# Versie_4.net
KiCad netlist of a schematic drawn in EAGLE
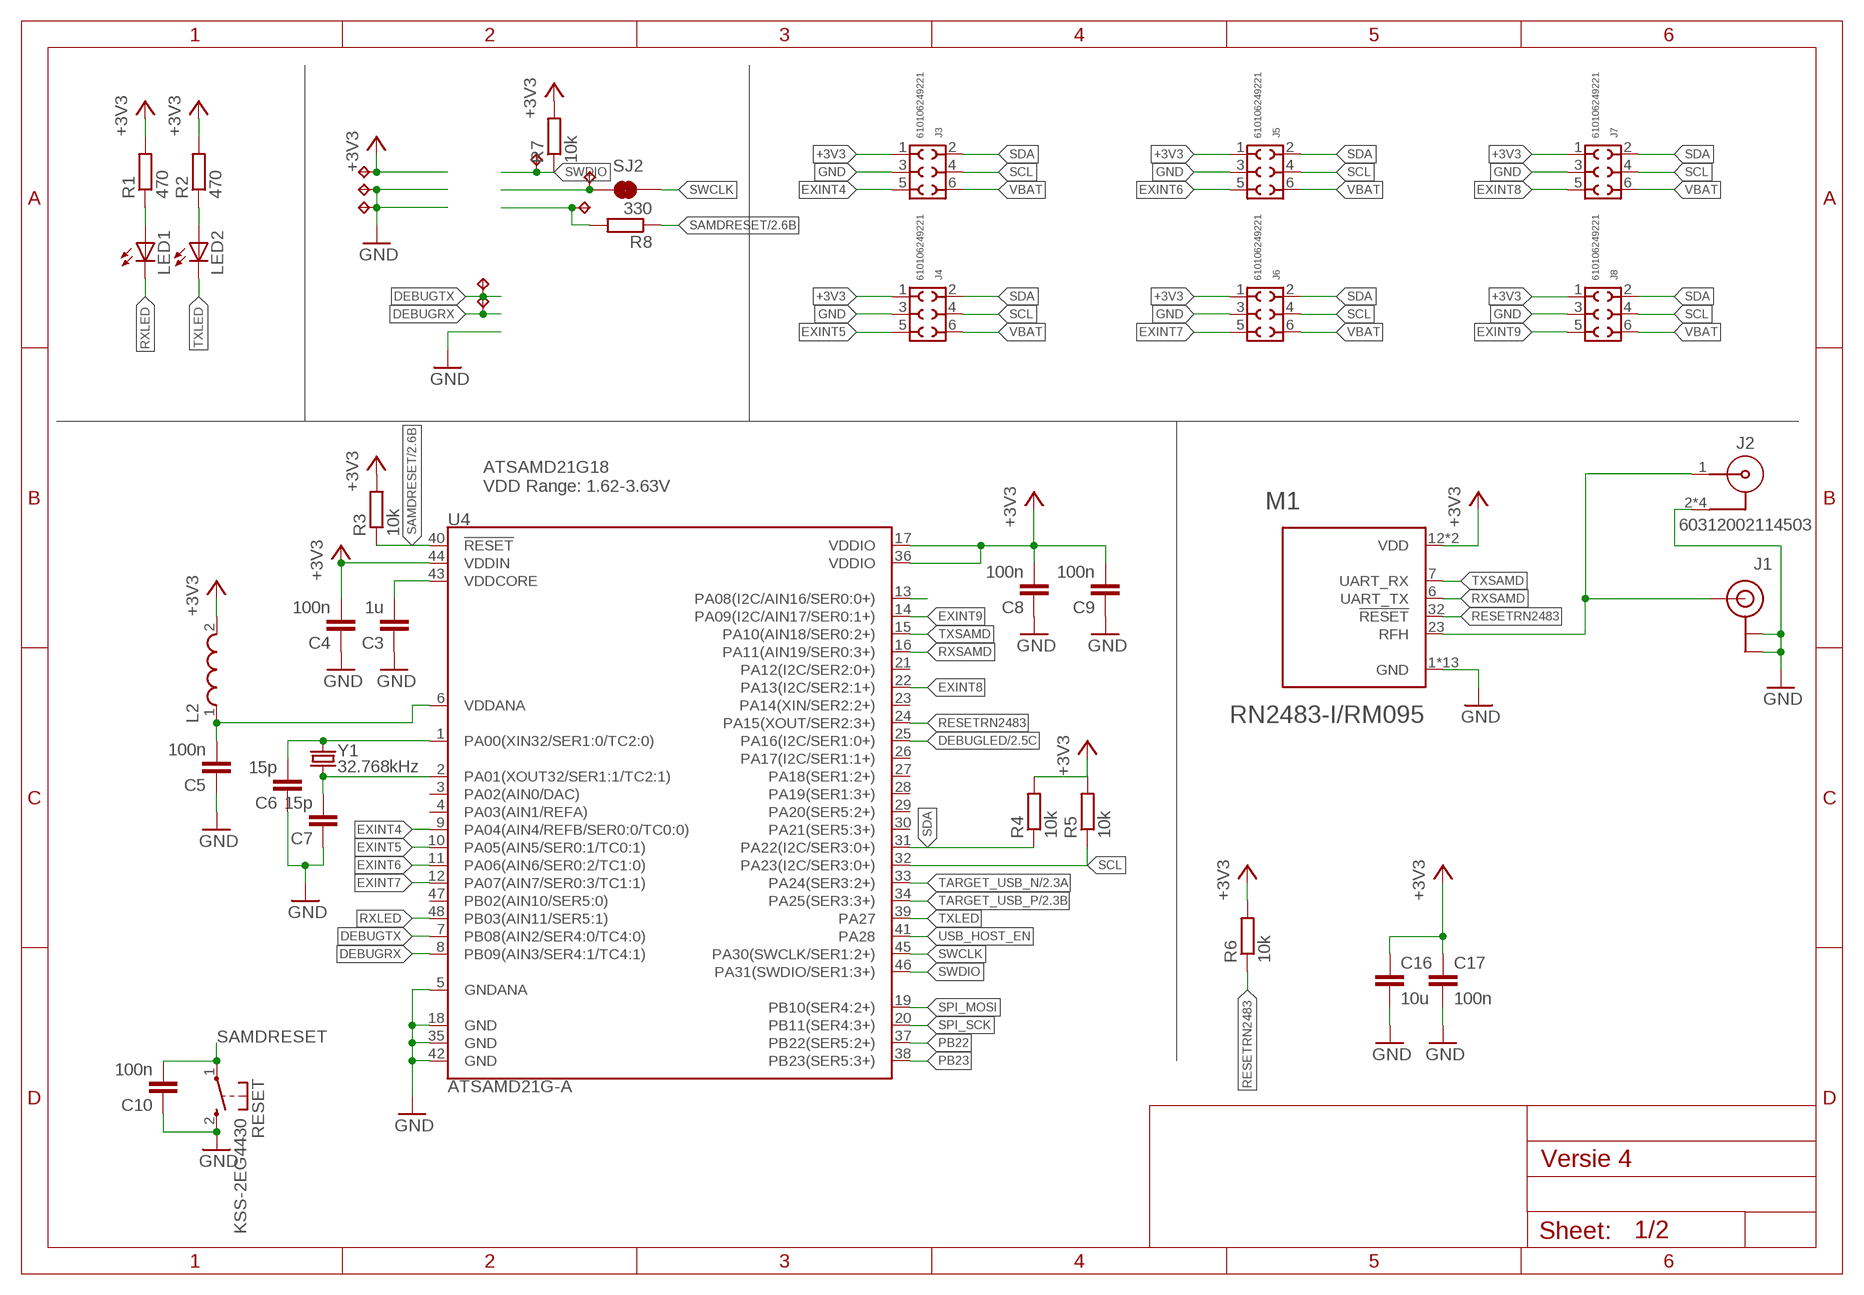
[diagram p0: schematic, sheet 1]
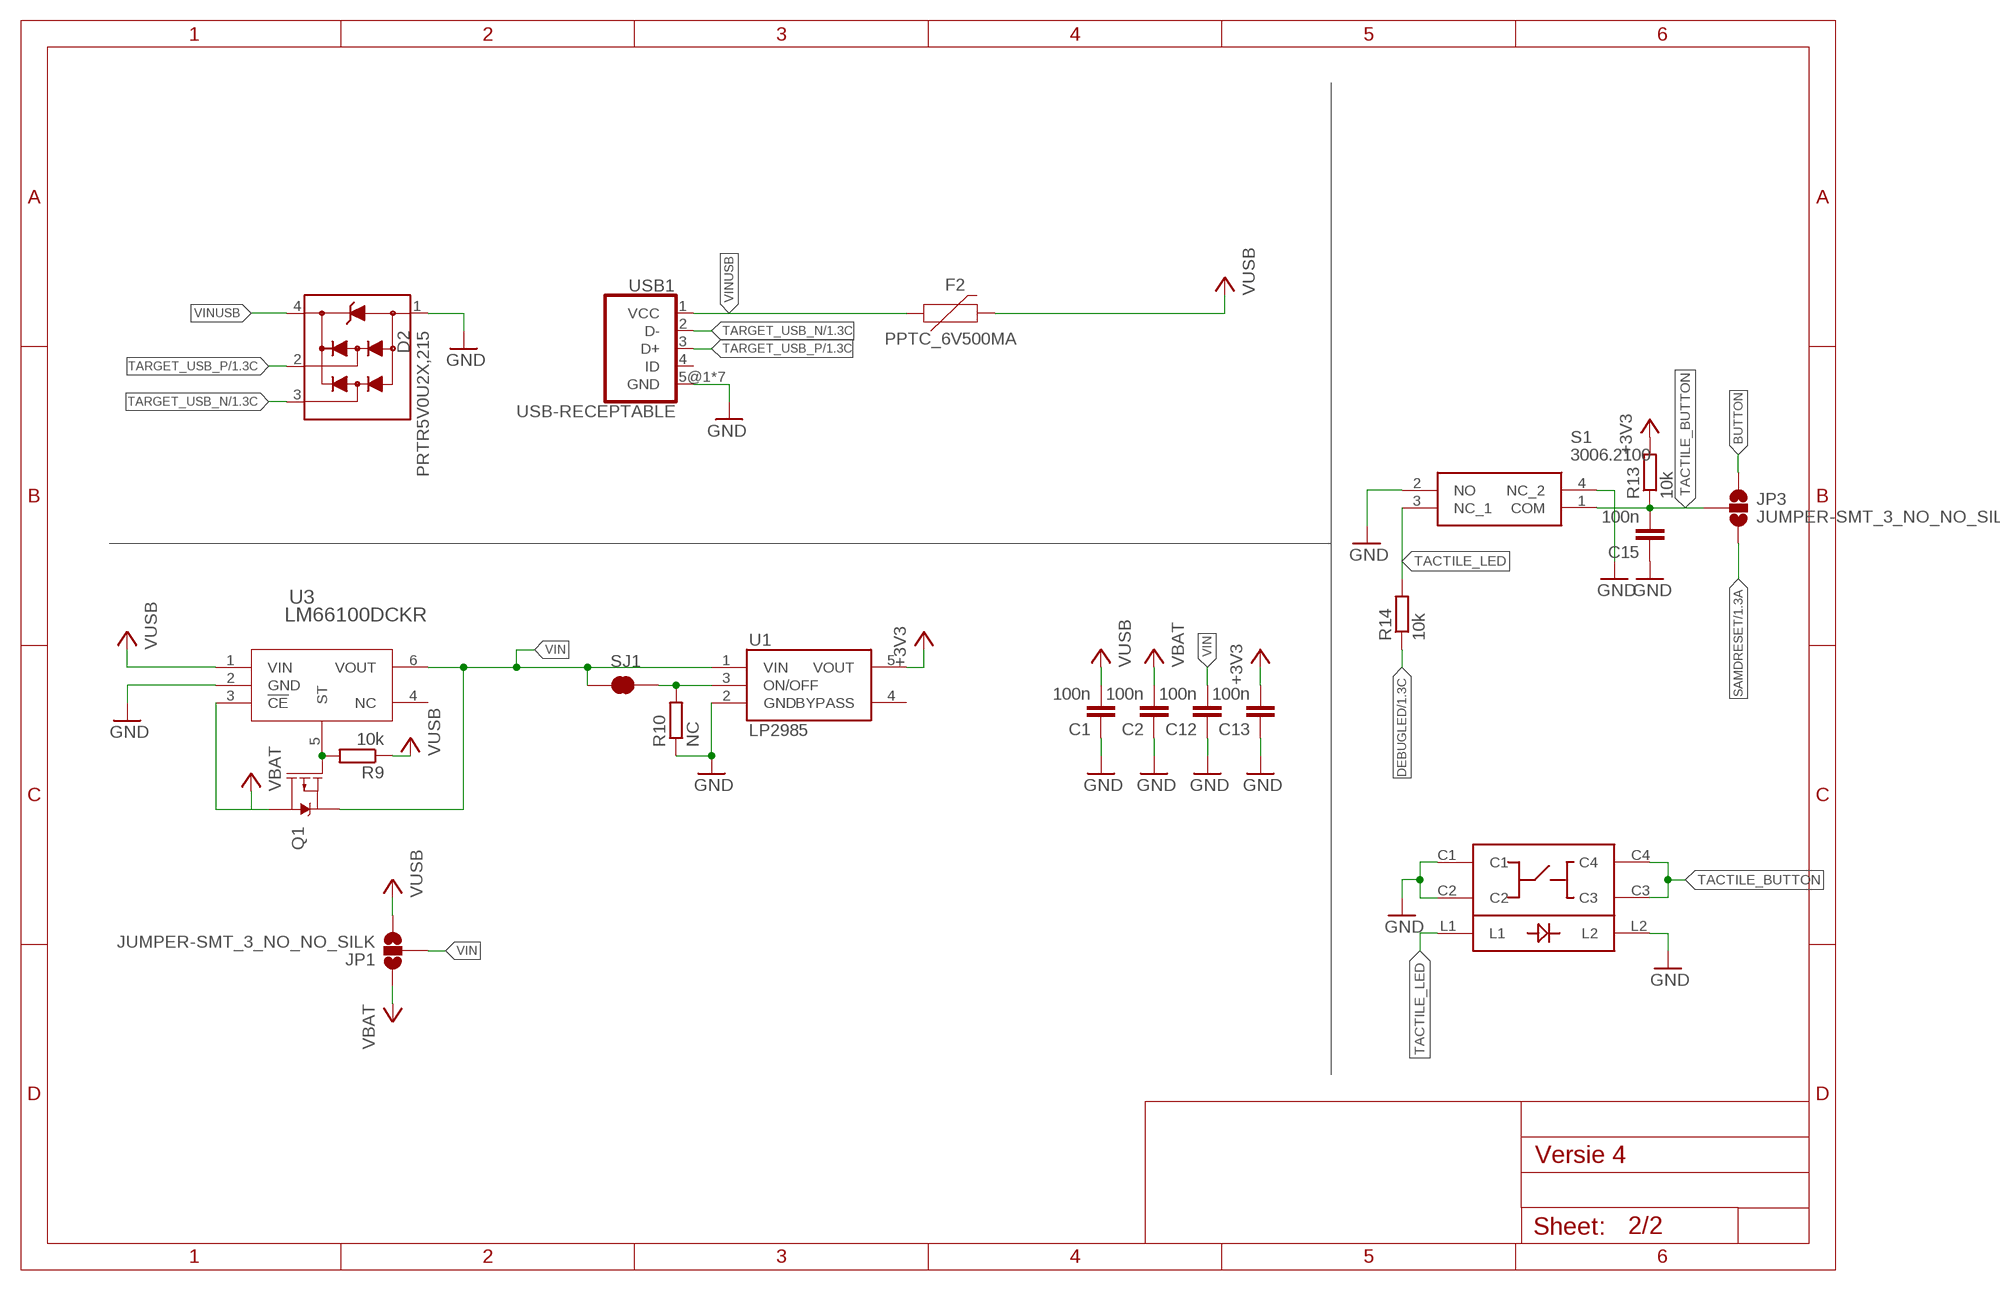
[diagram p1: schematic, sheet 2]

(export (version "E")
  (design (tool "Eeschema 10.0.6"))
  (components
    (comp (ref "C3")
      (value "1u")
      (footprint "eagle-import:C0603")
      (libsource (lib "eagle-import") (part "C-EUC0603"))
    )
    (comp (ref "C4")
      (value "100n")
      (footprint "eagle-import:C0603")
      (libsource (lib "eagle-import") (part "C-EUC0603"))
    )
    (comp (ref "C5")
      (value "100n")
      (footprint "eagle-import:C0603")
      (libsource (lib "eagle-import") (part "C-EUC0603"))
    )
    (comp (ref "C6")
      (value "15p")
      (footprint "eagle-import:C0603")
      (libsource (lib "eagle-import") (part "C-EUC0603"))
    )
    (comp (ref "C7")
      (value "15p")
      (footprint "eagle-import:C0603")
      (libsource (lib "eagle-import") (part "C-EUC0603"))
    )
    (comp (ref "C8")
      (value "100n")
      (footprint "eagle-import:C0603")
      (libsource (lib "eagle-import") (part "C-EUC0603"))
    )
    (comp (ref "C9")
      (value "100n")
      (footprint "eagle-import:C0603")
      (libsource (lib "eagle-import") (part "C-EUC0603"))
    )
    (comp (ref "C10")
      (value "100n")
      (footprint "eagle-import:C0603")
      (libsource (lib "eagle-import") (part "C-EUC0603"))
    )
    (comp (ref "C16")
      (value "10u")
      (footprint "eagle-import:C0805")
      (libsource (lib "eagle-import") (part "C-EUC0805"))
    )
    (comp (ref "C17")
      (value "100n")
      (footprint "eagle-import:C0603")
      (libsource (lib "eagle-import") (part "C-EUC0603"))
    )
    (comp (ref "J1")
      (value "U.FL")
      (footprint "eagle-import:U.FL")
      (libsource (lib "eagle-import") (part "U.FL"))
    )
    (comp (ref "J2")
      (value "60312002114503")
      (footprint "eagle-import:60312002114503")
      (libsource (lib "eagle-import") (part "60312002114503"))
    )
    (comp (ref "J3")
      (value "610106249221")
      (footprint "eagle-import:610106249221")
      (libsource (lib "eagle-import") (part "6101XX249221_610106249221"))
    )
    (comp (ref "J4")
      (value "610106249221")
      (footprint "eagle-import:610106249221")
      (libsource (lib "eagle-import") (part "6101XX249221_610106249221"))
    )
    (comp (ref "J5")
      (value "610106249221")
      (footprint "eagle-import:610106249221")
      (libsource (lib "eagle-import") (part "6101XX249221_610106249221"))
    )
    (comp (ref "J6")
      (value "610106249221")
      (footprint "eagle-import:610106249221")
      (libsource (lib "eagle-import") (part "6101XX249221_610106249221"))
    )
    (comp (ref "J7")
      (value "610106249221")
      (footprint "eagle-import:610106249221")
      (libsource (lib "eagle-import") (part "6101XX249221_610106249221"))
    )
    (comp (ref "J8")
      (value "610106249221")
      (footprint "eagle-import:610106249221")
      (libsource (lib "eagle-import") (part "6101XX249221_610106249221"))
    )
    (comp (ref "L2")
      (value "WE-CBA_0603(WB/HS)")
      (footprint "eagle-import:WE-CBA_0603(W=2.2)")
      (libsource (lib "eagle-import") (part "WE-CBA_0603(WB/HS)"))
    )
    (comp (ref "LED1")
      (value "LEDCHIP-LED0603")
      (footprint "eagle-import:CHIP-LED0603")
      (libsource (lib "eagle-import") (part "LEDCHIP-LED0603"))
    )
    (comp (ref "LED2")
      (value "LEDCHIP-LED0603")
      (footprint "eagle-import:CHIP-LED0603")
      (libsource (lib "eagle-import") (part "LEDCHIP-LED0603"))
    )
    (comp (ref "M1")
      (value "RN2483-I/RM095")
      (footprint "eagle-import:MICROCHIP_RN2483-I_RM095")
      (fields (field (name "MF") "Microchip Technology"))
      (libsource (lib "eagle-import") (part "RN2483-I/RM095"))
    )
    (comp (ref "R1")
      (value "470")
      (footprint "eagle-import:R0603")
      (libsource (lib "eagle-import") (part "R-EU_R0603"))
    )
    (comp (ref "R2")
      (value "470")
      (footprint "eagle-import:R0603")
      (libsource (lib "eagle-import") (part "R-EU_R0603"))
    )
    (comp (ref "R3")
      (value "10k")
      (footprint "eagle-import:R0603")
      (libsource (lib "eagle-import") (part "R-EU_R0603"))
    )
    (comp (ref "R4")
      (value "10k")
      (footprint "eagle-import:R0603")
      (libsource (lib "eagle-import") (part "R-EU_R0603"))
    )
    (comp (ref "R5")
      (value "10k")
      (footprint "eagle-import:R0603")
      (libsource (lib "eagle-import") (part "R-EU_R0603"))
    )
    (comp (ref "R6")
      (value "10k")
      (footprint "eagle-import:R0603")
      (libsource (lib "eagle-import") (part "R-EU_R0603"))
    )
    (comp (ref "R7")
      (value "10k")
      (footprint "eagle-import:R0603")
      (libsource (lib "eagle-import") (part "R-EU_R0603"))
    )
    (comp (ref "R8")
      (value "330")
      (footprint "eagle-import:R0603")
      (libsource (lib "eagle-import") (part "R-EU_R0603"))
    )
    (comp (ref "RESET")
      (value "KSS-2EG4430")
      (footprint "eagle-import:KSS-2EG4430")
      (libsource (lib "eagle-import") (part "KSS-2EG4430"))
    )
    (comp (ref "SJ2")
      (value "JUMPER-PAD-2-NC_BY_TRACENO_SILK")
      (footprint "eagle-import:PAD-JUMPER-2-NC_BY_TRACE_NO_SILK")
      (libsource (lib "eagle-import") (part "JUMPER-PAD-2-NC_BY_TRACENO_SILK"))
    )
    (comp (ref "TP1")
      (value "TPB1,27")
      (footprint "eagle-import:B1,27")
      (libsource (lib "eagle-import") (part "TPB1,27"))
    )
    (comp (ref "TP2")
      (value "TPB1,27")
      (footprint "eagle-import:B1,27")
      (libsource (lib "eagle-import") (part "TPB1,27"))
    )
    (comp (ref "TP3")
      (value "TPB1,27")
      (footprint "eagle-import:B1,27")
      (libsource (lib "eagle-import") (part "TPB1,27"))
    )
    (comp (ref "TP4")
      (value "TPB1,27")
      (footprint "eagle-import:B1,27")
      (libsource (lib "eagle-import") (part "TPB1,27"))
    )
    (comp (ref "TP5")
      (value "TPB1,27")
      (footprint "eagle-import:B1,27")
      (libsource (lib "eagle-import") (part "TPB1,27"))
    )
    (comp (ref "TP6")
      (value "TPB1,27")
      (footprint "eagle-import:B1,27")
      (libsource (lib "eagle-import") (part "TPB1,27"))
    )
    (comp (ref "TP7")
      (value "TPB1,27")
      (footprint "eagle-import:B1,27")
      (libsource (lib "eagle-import") (part "TPB1,27"))
    )
    (comp (ref "TP8")
      (value "TPB1,27")
      (footprint "eagle-import:B1,27")
      (libsource (lib "eagle-import") (part "TPB1,27"))
    )
    (comp (ref "U4")
      (value "ATSAMD21G-A")
      (footprint "eagle-import:TQFP-48")
      (libsource (lib "eagle-import") (part "ATSAMD21G-A"))
    )
    (comp (ref "Y1")
      (value "32.768kHz")
      (footprint "eagle-import:CRYSTAL-SMD-3.2X1.5MM")
      (libsource (lib "eagle-import") (part "CRYSTAL3.2X1.5MM"))
    )
    (comp (ref "C1")
      (value "100n")
      (footprint "eagle-import:C0603")
      (libsource (lib "eagle-import") (part "C-EUC0603"))
    )
    (comp (ref "C2")
      (value "100n")
      (footprint "eagle-import:C0603")
      (libsource (lib "eagle-import") (part "C-EUC0603"))
    )
    (comp (ref "C12")
      (value "100n")
      (footprint "eagle-import:C0603")
      (libsource (lib "eagle-import") (part "C-EUC0603"))
    )
    (comp (ref "C13")
      (value "100n")
      (footprint "eagle-import:C0603")
      (libsource (lib "eagle-import") (part "C-EUC0603"))
    )
    (comp (ref "C15")
      (value "100n")
      (footprint "eagle-import:C0603")
      (libsource (lib "eagle-import") (part "C-EUC0603"))
    )
    (comp (ref "D2")
      (value "PRTR5V0U2X,215")
      (footprint "eagle-import:SOT143B")
      (fields (field (name "MF") "Nexperia USA Inc."))
      (libsource (lib "eagle-import") (part "PRTR5V0U2X,215"))
    )
    (comp (ref "F2")
      (value "PPTC_6V500MA")
      (footprint "eagle-import:0805")
      (libsource (lib "eagle-import") (part "PPTC_6V500MA"))
    )
    (comp (ref "JP1")
      (value "JUMPER-SMT_3_NO_NO_SILK")
      (footprint "eagle-import:SMT-JUMPER_3_0-NO_TRACE_NO-SILK")
      (libsource (lib "eagle-import") (part "JUMPER-SMT_3_NO_NO_SILK"))
    )
    (comp (ref "JP3")
      (value "JUMPER-SMT_3_NO_NO_SILK")
      (footprint "eagle-import:SMT-JUMPER_3_0-NO_TRACE_NO-SILK")
      (libsource (lib "eagle-import") (part "JUMPER-SMT_3_NO_NO_SILK"))
    )
    (comp (ref "Q1")
      (value "MOSFET_PCH-DMG2307L")
      (footprint "eagle-import:SOT23-3")
      (libsource (lib "eagle-import") (part "MOSFET_PCH-DMG2307L"))
    )
    (comp (ref "R9")
      (value "10k")
      (footprint "eagle-import:R0603")
      (libsource (lib "eagle-import") (part "R-EU_R0603"))
    )
    (comp (ref "R10")
      (value "NC")
      (footprint "eagle-import:R0603")
      (libsource (lib "eagle-import") (part "R-EU_R0603"))
    )
    (comp (ref "R13")
      (value "10k")
      (footprint "eagle-import:R0603")
      (libsource (lib "eagle-import") (part "R-EU_R0603"))
    )
    (comp (ref "R14")
      (value "10k")
      (footprint "eagle-import:R0603")
      (libsource (lib "eagle-import") (part "R-EU_R0603"))
    )
    (comp (ref "S1")
      (value "3006.2100")
      (footprint "eagle-import:30062101")
      (fields (field (name "MOUSER_PART_NUMBER") "979-3006.2100"))
      (libsource (lib "eagle-import") (part "3006.2100"))
    )
    (comp (ref "SJ1")
      (value "JUMPER-PAD-2-NC_BY_TRACENO_SILK")
      (footprint "eagle-import:PAD-JUMPER-2-NC_BY_TRACE_NO_SILK")
      (libsource (lib "eagle-import") (part "JUMPER-PAD-2-NC_BY_TRACENO_SILK"))
    )
    (comp (ref "U$1")
      (value "LS1201")
      (footprint "eagle-import:LS1201")
      (libsource (lib "eagle-import") (part "LS1201"))
    )
    (comp (ref "U1")
      (value "LP2985AIM5-3.3")
      (footprint "eagle-import:SOT25")
      (libsource (lib "eagle-import") (part "LP2985AIM5-3.3"))
    )
    (comp (ref "U3")
      (value "LM66100DCKR")
      (footprint "eagle-import:DCK6_TEX")
      (fields (field (name "COPYRIGHT") "Copyright (C) 2018 Accelerated Designs. All rights reserved"))
      (libsource (lib "eagle-import") (part "LM66100DCKR"))
    )
    (comp (ref "USB1")
      (value "USB-RECEPTABLE")
      (footprint "eagle-import:FCI-10103594-0001LF")
      (libsource (lib "eagle-import") (part "USB-RECEPTABLE"))
    )
  )
  (nets
    (net (code "1") (name "+3V3") (class "Default")
      (node (ref "C13") (pin "2") (pinfunction "2_2") (pintype "passive"))
      (node (ref "C16") (pin "1") (pinfunction "1_1") (pintype "passive"))
      (node (ref "C17") (pin "1") (pinfunction "1_1") (pintype "passive"))
      (node (ref "C4") (pin "2") (pinfunction "2_2") (pintype "passive"))
      (node (ref "C8") (pin "2") (pinfunction "2_2") (pintype "passive"))
      (node (ref "C9") (pin "2") (pinfunction "2_2") (pintype "passive"))
      (node (ref "J3") (pin "1") (pinfunction "1_1") (pintype "passive"))
      (node (ref "J4") (pin "1") (pinfunction "1_1") (pintype "passive"))
      (node (ref "J5") (pin "1") (pinfunction "1_1") (pintype "passive"))
      (node (ref "J6") (pin "1") (pinfunction "1_1") (pintype "passive"))
      (node (ref "J7") (pin "1") (pinfunction "1_1") (pintype "passive"))
      (node (ref "J8") (pin "1") (pinfunction "1_1") (pintype "passive"))
      (node (ref "L2") (pin "2") (pinfunction "2_2") (pintype "passive"))
      (node (ref "M1") (pin "12") (pinfunction "VDD_12") (pintype "power_in"))
      (node (ref "M1") (pin "34") (pinfunction "VDD_34") (pintype "power_in"))
      (node (ref "R1") (pin "2") (pinfunction "2_2") (pintype "passive"))
      (node (ref "R13") (pin "2") (pinfunction "2_2") (pintype "passive"))
      (node (ref "R2") (pin "2") (pinfunction "2_2") (pintype "passive"))
      (node (ref "R3") (pin "2") (pinfunction "2_2") (pintype "passive"))
      (node (ref "R4") (pin "2") (pinfunction "2_2") (pintype "passive"))
      (node (ref "R5") (pin "2") (pinfunction "2_2") (pintype "passive"))
      (node (ref "R6") (pin "2") (pinfunction "2_2") (pintype "passive"))
      (node (ref "R7") (pin "2") (pinfunction "2_2") (pintype "passive"))
      (node (ref "TP1") (pin "TP") (pinfunction "TP_TP") (pintype "input"))
      (node (ref "U1") (pin "5") (pinfunction "VOUT_5") (pintype "power_in"))
      (node (ref "U4") (pin "17") (pinfunction "VDDIO_17") (pintype "bidirectional"))
      (node (ref "U4") (pin "36") (pinfunction "VDDIO_36") (pintype "bidirectional"))
      (node (ref "U4") (pin "44") (pinfunction "VDDIN_44") (pintype "bidirectional"))
    )
    (net (code "2") (name "BUTTON") (class "Default")
      (node (ref "JP3") (pin "1") (pinfunction "1_1") (pintype "passive"))
      (node (ref "U4") (pin "13") (pinfunction "PA08(I2C/AIN16/SER0:0+)_13") (pintype "bidirectional"))
    )
    (net (code "3") (name "BYPASS") (class "Default")
      (node (ref "U1") (pin "4") (pinfunction "BYPASS_4") (pintype "power_in"))
    )
    (net (code "4") (name "DEBUGLED") (class "Default")
      (node (ref "R14") (pin "1") (pinfunction "1_1") (pintype "passive"))
      (node (ref "U4") (pin "25") (pinfunction "PA16(I2C/SER1:0+)_25") (pintype "bidirectional"))
    )
    (net (code "5") (name "DEBUGRX") (class "Default")
      (node (ref "TP8") (pin "TP") (pinfunction "TP_TP") (pintype "input"))
      (node (ref "U4") (pin "8") (pinfunction "PB09(AIN3/SER4:1/TC4:1)_8") (pintype "bidirectional"))
    )
    (net (code "6") (name "DEBUGTX") (class "Default")
      (node (ref "TP7") (pin "TP") (pinfunction "TP_TP") (pintype "input"))
      (node (ref "U4") (pin "7") (pinfunction "PB08(AIN2/SER4:0/TC4:0)_7") (pintype "bidirectional"))
    )
    (net (code "7") (name "EXINT4") (class "Default")
      (node (ref "J3") (pin "5") (pinfunction "5_5") (pintype "passive"))
      (node (ref "U4") (pin "9") (pinfunction "PA04(AIN4/REFB/SER0:0/TC0:0)_9") (pintype "bidirectional"))
    )
    (net (code "8") (name "EXINT5") (class "Default")
      (node (ref "J4") (pin "5") (pinfunction "5_5") (pintype "passive"))
      (node (ref "U4") (pin "10") (pinfunction "PA05(AIN5/SER0:1/TC0:1)_10") (pintype "bidirectional"))
    )
    (net (code "9") (name "EXINT6") (class "Default")
      (node (ref "J5") (pin "5") (pinfunction "5_5") (pintype "passive"))
      (node (ref "U4") (pin "11") (pinfunction "PA06(AIN6/SER0:2/TC1:0)_11") (pintype "bidirectional"))
    )
    (net (code "10") (name "EXINT7") (class "Default")
      (node (ref "J6") (pin "5") (pinfunction "5_5") (pintype "passive"))
      (node (ref "U4") (pin "12") (pinfunction "PA07(AIN7/SER0:3/TC1:1)_12") (pintype "bidirectional"))
    )
    (net (code "11") (name "EXINT8") (class "Default")
      (node (ref "J7") (pin "5") (pinfunction "5_5") (pintype "passive"))
      (node (ref "U4") (pin "22") (pinfunction "PA13(I2C/SER2:1+)_22") (pintype "bidirectional"))
    )
    (net (code "12") (name "EXINT9") (class "Default")
      (node (ref "J8") (pin "5") (pinfunction "5_5") (pintype "passive"))
      (node (ref "U4") (pin "14") (pinfunction "PA09(I2C/AIN17/SER0:1+)_14") (pintype "bidirectional"))
    )
    (net (code "13") (name "GND") (class "Default")
      (node (ref "C1") (pin "1") (pinfunction "1_1") (pintype "passive"))
      (node (ref "C10") (pin "1") (pinfunction "1_1") (pintype "passive"))
      (node (ref "C12") (pin "1") (pinfunction "1_1") (pintype "passive"))
      (node (ref "C13") (pin "1") (pinfunction "1_1") (pintype "passive"))
      (node (ref "C15") (pin "1") (pinfunction "1_1") (pintype "passive"))
      (node (ref "C16") (pin "2") (pinfunction "2_2") (pintype "passive"))
      (node (ref "C17") (pin "2") (pinfunction "2_2") (pintype "passive"))
      (node (ref "C2") (pin "1") (pinfunction "1_1") (pintype "passive"))
      (node (ref "C3") (pin "1") (pinfunction "1_1") (pintype "passive"))
      (node (ref "C4") (pin "1") (pinfunction "1_1") (pintype "passive"))
      (node (ref "C5") (pin "1") (pinfunction "1_1") (pintype "passive"))
      (node (ref "C6") (pin "1") (pinfunction "1_1") (pintype "passive"))
      (node (ref "C7") (pin "1") (pinfunction "1_1") (pintype "passive"))
      (node (ref "C8") (pin "1") (pinfunction "1_1") (pintype "passive"))
      (node (ref "C9") (pin "1") (pinfunction "1_1") (pintype "passive"))
      (node (ref "D2") (pin "1") (pinfunction "P$1_1") (pintype "passive"))
      (node (ref "J1") (pin "P$1") (pinfunction "GND_P$1") (pintype "bidirectional"))
      (node (ref "J1") (pin "P$2") (pinfunction "GND_P$2") (pintype "bidirectional"))
      (node (ref "J2") (pin "2") (pinfunction "2_2") (pintype "passive"))
      (node (ref "J2") (pin "3") (pinfunction "2_3") (pintype "passive"))
      (node (ref "J2") (pin "4") (pinfunction "2_4") (pintype "passive"))
      (node (ref "J2") (pin "5") (pinfunction "2_5") (pintype "passive"))
      (node (ref "J3") (pin "3") (pinfunction "3_3") (pintype "passive"))
      (node (ref "J4") (pin "3") (pinfunction "3_3") (pintype "passive"))
      (node (ref "J5") (pin "3") (pinfunction "3_3") (pintype "passive"))
      (node (ref "J6") (pin "3") (pinfunction "3_3") (pintype "passive"))
      (node (ref "J7") (pin "3") (pinfunction "3_3") (pintype "passive"))
      (node (ref "J8") (pin "3") (pinfunction "3_3") (pintype "passive"))
      (node (ref "M1") (pin "1") (pinfunction "GND_1") (pintype "passive"))
      (node (ref "M1") (pin "11") (pinfunction "GND_11") (pintype "passive"))
      (node (ref "M1") (pin "20") (pinfunction "GND_20") (pintype "passive"))
      (node (ref "M1") (pin "21") (pinfunction "GND_21") (pintype "passive"))
      (node (ref "M1") (pin "22") (pinfunction "GND_22") (pintype "passive"))
      (node (ref "M1") (pin "24") (pinfunction "GND_24") (pintype "passive"))
      (node (ref "M1") (pin "26") (pinfunction "GND_26") (pintype "passive"))
      (node (ref "M1") (pin "27") (pinfunction "GND_27") (pintype "passive"))
      (node (ref "M1") (pin "28") (pinfunction "GND_28") (pintype "passive"))
      (node (ref "M1") (pin "33") (pinfunction "GND_33") (pintype "passive"))
      (node (ref "M1") (pin "41") (pinfunction "GND_41") (pintype "passive"))
      (node (ref "M1") (pin "47") (pinfunction "GND_47") (pintype "passive"))
      (node (ref "M1") (pin "8") (pinfunction "GND_8") (pintype "passive"))
      (node (ref "R10") (pin "1") (pinfunction "1_1") (pintype "passive"))
      (node (ref "RESET") (pin "2") (pinfunction "S_2") (pintype "passive"))
      (node (ref "S1") (pin "2") (pinfunction "NO_2") (pintype "bidirectional"))
      (node (ref "S1") (pin "4") (pinfunction "NC_2_4") (pintype "bidirectional"))
      (node (ref "TP2") (pin "TP") (pinfunction "TP_TP") (pintype "input"))
      (node (ref "TP3") (pin "TP") (pinfunction "TP_TP") (pintype "input"))
      (node (ref "U$1") (pin "C1") (pinfunction "C1_C1") (pintype "bidirectional"))
      (node (ref "U$1") (pin "C2") (pinfunction "C2_C2") (pintype "bidirectional"))
      (node (ref "U$1") (pin "L2") (pinfunction "L2_L2") (pintype "bidirectional"))
      (node (ref "U1") (pin "2") (pinfunction "GND_2") (pintype "power_in"))
      (node (ref "U3") (pin "2") (pinfunction "GND_2") (pintype "power_in"))
      (node (ref "U4") (pin "18") (pinfunction "GND_18") (pintype "bidirectional"))
      (node (ref "U4") (pin "35") (pinfunction "GND_35") (pintype "bidirectional"))
      (node (ref "U4") (pin "42") (pinfunction "GND_42") (pintype "bidirectional"))
      (node (ref "U4") (pin "5") (pinfunction "GNDANA_5") (pintype "bidirectional"))
      (node (ref "USB1") (pin "5@1") (pinfunction "GND_5@1") (pintype "bidirectional"))
      (node (ref "USB1") (pin "5@2") (pinfunction "GND_5@2") (pintype "bidirectional"))
      (node (ref "USB1") (pin "5@3") (pinfunction "GND_5@3") (pintype "bidirectional"))
      (node (ref "USB1") (pin "5@4") (pinfunction "GND_5@4") (pintype "bidirectional"))
      (node (ref "USB1") (pin "5@5") (pinfunction "GND_5@5") (pintype "bidirectional"))
      (node (ref "USB1") (pin "5@6") (pinfunction "GND_5@6") (pintype "bidirectional"))
      (node (ref "USB1") (pin "5@7") (pinfunction "GND_5@7") (pintype "bidirectional"))
    )
    (net (code "14") (name "Net-(J1-SIGNAL)") (class "Default")
      (node (ref "J1") (pin "P$3") (pinfunction "SIGNAL_P$3") (pintype "bidirectional"))
      (node (ref "J2") (pin "1") (pinfunction "1_1") (pintype "passive"))
      (node (ref "M1") (pin "23") (pinfunction "RFH_23") (pintype "input"))
    )
    (net (code "15") (name "Net-(LED1-PadA)") (class "Default")
      (node (ref "LED1") (pin "A") (pinfunction "A_A") (pintype "passive"))
      (node (ref "R1") (pin "1") (pinfunction "1_1") (pintype "passive"))
    )
    (net (code "16") (name "Net-(LED2-PadA)") (class "Default")
      (node (ref "LED2") (pin "A") (pinfunction "A_A") (pintype "passive"))
      (node (ref "R2") (pin "1") (pinfunction "1_1") (pintype "passive"))
    )
    (net (code "17") (name "Net-(Q1-G)") (class "Default")
      (node (ref "Q1") (pin "1") (pinfunction "G_1") (pintype "bidirectional"))
      (node (ref "R9") (pin "2") (pinfunction "2_2") (pintype "passive"))
      (node (ref "U3") (pin "5") (pinfunction "ST_5") (pintype "output"))
    )
    (net (code "18") (name "Net-(R8-Pad2)") (class "Default")
      (node (ref "R8") (pin "2") (pinfunction "2_2") (pintype "passive"))
      (node (ref "TP6") (pin "TP") (pinfunction "TP_TP") (pintype "input"))
    )
    (net (code "19") (name "Net-(SJ2-Pad2)") (class "Default")
      (node (ref "SJ2") (pin "2") (pinfunction "2_2") (pintype "passive"))
      (node (ref "TP5") (pin "TP") (pinfunction "TP_TP") (pintype "input"))
    )
    (net (code "20") (name "Net-(U1-ON{slash}OFF)") (class "Default")
      (node (ref "R10") (pin "2") (pinfunction "2_2") (pintype "passive"))
      (node (ref "SJ1") (pin "1") (pinfunction "1_1") (pintype "passive"))
      (node (ref "U1") (pin "3") (pinfunction "ON/OFF_3") (pintype "input"))
    )
    (net (code "21") (name "Net-(U4-PA00(XIN32{slash}SER1:0{slash}TC2:0))") (class "Default")
      (node (ref "C6") (pin "2") (pinfunction "2_2") (pintype "passive"))
      (node (ref "U4") (pin "1") (pinfunction "PA00(XIN32/SER1:0/TC2:0)_1") (pintype "bidirectional"))
      (node (ref "Y1") (pin "P$2") (pinfunction "2_P$2") (pintype "passive"))
    )
    (net (code "22") (name "Net-(U4-PA01(XOUT32{slash}SER1:1{slash}TC2:1))") (class "Default")
      (node (ref "C7") (pin "2") (pinfunction "2_2") (pintype "passive"))
      (node (ref "U4") (pin "2") (pinfunction "PA01(XOUT32/SER1:1/TC2:1)_2") (pintype "bidirectional"))
      (node (ref "Y1") (pin "P$1") (pinfunction "1_P$1") (pintype "passive"))
    )
    (net (code "23") (name "Net-(U4-VDDANA)") (class "Default")
      (node (ref "C5") (pin "2") (pinfunction "2_2") (pintype "passive"))
      (node (ref "L2") (pin "1") (pinfunction "1_1") (pintype "passive"))
      (node (ref "U4") (pin "6") (pinfunction "VDDANA_6") (pintype "bidirectional"))
    )
    (net (code "24") (name "Net-(U4-VDDCORE)") (class "Default")
      (node (ref "C3") (pin "2") (pinfunction "2_2") (pintype "passive"))
      (node (ref "U4") (pin "43") (pinfunction "VDDCORE_43") (pintype "bidirectional"))
    )
    (net (code "25") (name "PB22") (class "Default")
      (node (ref "U4") (pin "37") (pinfunction "PB22(SER5:2+)_37") (pintype "bidirectional"))
    )
    (net (code "26") (name "PB23") (class "Default")
      (node (ref "U4") (pin "38") (pinfunction "PB23(SER5:3+)_38") (pintype "bidirectional"))
    )
    (net (code "27") (name "RESETRN2483") (class "Default")
      (node (ref "M1") (pin "32") (pinfunction "~{RESET}_32") (pintype "input"))
      (node (ref "R6") (pin "1") (pinfunction "1_1") (pintype "passive"))
      (node (ref "U4") (pin "24") (pinfunction "PA15(XOUT/SER2:3+)_24") (pintype "bidirectional"))
    )
    (net (code "28") (name "RXLED") (class "Default")
      (node (ref "LED1") (pin "C") (pinfunction "C_C") (pintype "passive"))
      (node (ref "U4") (pin "48") (pinfunction "PB03(AIN11/SER5:1)_48") (pintype "bidirectional"))
    )
    (net (code "29") (name "RXSAMD") (class "Default")
      (node (ref "M1") (pin "6") (pinfunction "UART_TX_6") (pintype "output"))
      (node (ref "U4") (pin "16") (pinfunction "PA11(AIN19/SER0:3+)_16") (pintype "bidirectional"))
    )
    (net (code "30") (name "SAMDRESET") (class "Default")
      (node (ref "C10") (pin "2") (pinfunction "2_2") (pintype "passive"))
      (node (ref "JP3") (pin "3") (pinfunction "3_3") (pintype "passive"))
      (node (ref "R3") (pin "1") (pinfunction "1_1") (pintype "passive"))
      (node (ref "R8") (pin "1") (pinfunction "1_1") (pintype "passive"))
      (node (ref "RESET") (pin "1") (pinfunction "P_1") (pintype "passive"))
      (node (ref "U4") (pin "40") (pinfunction "~{RESET}_40") (pintype "bidirectional"))
    )
    (net (code "31") (name "SCL") (class "Default")
      (node (ref "J3") (pin "4") (pinfunction "4_4") (pintype "passive"))
      (node (ref "J4") (pin "4") (pinfunction "4_4") (pintype "passive"))
      (node (ref "J5") (pin "4") (pinfunction "4_4") (pintype "passive"))
      (node (ref "J6") (pin "4") (pinfunction "4_4") (pintype "passive"))
      (node (ref "J7") (pin "4") (pinfunction "4_4") (pintype "passive"))
      (node (ref "J8") (pin "4") (pinfunction "4_4") (pintype "passive"))
      (node (ref "R5") (pin "1") (pinfunction "1_1") (pintype "passive"))
      (node (ref "U4") (pin "32") (pinfunction "PA23(I2C/SER3:0+)_32") (pintype "bidirectional"))
    )
    (net (code "32") (name "SDA") (class "Default")
      (node (ref "J3") (pin "2") (pinfunction "2_2") (pintype "passive"))
      (node (ref "J4") (pin "2") (pinfunction "2_2") (pintype "passive"))
      (node (ref "J5") (pin "2") (pinfunction "2_2") (pintype "passive"))
      (node (ref "J6") (pin "2") (pinfunction "2_2") (pintype "passive"))
      (node (ref "J7") (pin "2") (pinfunction "2_2") (pintype "passive"))
      (node (ref "J8") (pin "2") (pinfunction "2_2") (pintype "passive"))
      (node (ref "R4") (pin "1") (pinfunction "1_1") (pintype "passive"))
      (node (ref "U4") (pin "31") (pinfunction "PA22(I2C/SER3:0+)_31") (pintype "bidirectional"))
    )
    (net (code "33") (name "SPI_MOSI") (class "Default")
      (node (ref "U4") (pin "19") (pinfunction "PB10(SER4:2+)_19") (pintype "bidirectional"))
    )
    (net (code "34") (name "SPI_SCK") (class "Default")
      (node (ref "U4") (pin "20") (pinfunction "PB11(SER4:3+)_20") (pintype "bidirectional"))
    )
    (net (code "35") (name "SWCLK") (class "Default")
      (node (ref "SJ2") (pin "1") (pinfunction "1_1") (pintype "passive"))
      (node (ref "U4") (pin "45") (pinfunction "PA30(SWCLK/SER1:2+)_45") (pintype "bidirectional"))
    )
    (net (code "36") (name "SWDIO") (class "Default")
      (node (ref "R7") (pin "1") (pinfunction "1_1") (pintype "passive"))
      (node (ref "TP4") (pin "TP") (pinfunction "TP_TP") (pintype "input"))
      (node (ref "U4") (pin "46") (pinfunction "PA31(SWDIO/SER1:3+)_46") (pintype "bidirectional"))
    )
    (net (code "37") (name "TACTILE_BUTTON") (class "Default")
      (node (ref "C15") (pin "2") (pinfunction "2_2") (pintype "passive"))
      (node (ref "JP3") (pin "2") (pinfunction "2_2") (pintype "passive"))
      (node (ref "R13") (pin "1") (pinfunction "1_1") (pintype "passive"))
      (node (ref "S1") (pin "1") (pinfunction "COM_1") (pintype "bidirectional"))
      (node (ref "U$1") (pin "C3") (pinfunction "C3_C3") (pintype "bidirectional"))
      (node (ref "U$1") (pin "C4") (pinfunction "C4_C4") (pintype "bidirectional"))
    )
    (net (code "38") (name "TACTILE_LED") (class "Default")
      (node (ref "R14") (pin "2") (pinfunction "2_2") (pintype "passive"))
      (node (ref "S1") (pin "3") (pinfunction "NC_1_3") (pintype "bidirectional"))
      (node (ref "U$1") (pin "L1") (pinfunction "L1_L1") (pintype "bidirectional"))
    )
    (net (code "39") (name "TARGET_USB_N") (class "Default")
      (node (ref "D2") (pin "3") (pinfunction "P$3_3") (pintype "passive"))
      (node (ref "U4") (pin "33") (pinfunction "PA24(SER3:2+)_33") (pintype "bidirectional"))
      (node (ref "USB1") (pin "2") (pinfunction "D-_2") (pintype "bidirectional"))
    )
    (net (code "40") (name "TARGET_USB_P") (class "Default")
      (node (ref "D2") (pin "2") (pinfunction "P$2_2") (pintype "passive"))
      (node (ref "U4") (pin "34") (pinfunction "PA25(SER3:3+)_34") (pintype "bidirectional"))
      (node (ref "USB1") (pin "3") (pinfunction "D+_3") (pintype "bidirectional"))
    )
    (net (code "41") (name "TXLED") (class "Default")
      (node (ref "LED2") (pin "C") (pinfunction "C_C") (pintype "passive"))
      (node (ref "U4") (pin "39") (pinfunction "PA27_39") (pintype "bidirectional"))
    )
    (net (code "42") (name "TXSAMD") (class "Default")
      (node (ref "M1") (pin "7") (pinfunction "UART_RX_7") (pintype "input"))
      (node (ref "U4") (pin "15") (pinfunction "PA10(AIN18/SER0:2+)_15") (pintype "bidirectional"))
    )
    (net (code "43") (name "USB_HOST_EN") (class "Default")
      (node (ref "U4") (pin "41") (pinfunction "PA28_41") (pintype "bidirectional"))
    )
    (net (code "44") (name "VBAT") (class "Default")
      (node (ref "C2") (pin "2") (pinfunction "2_2") (pintype "passive"))
      (node (ref "J3") (pin "6") (pinfunction "6_6") (pintype "passive"))
      (node (ref "J4") (pin "6") (pinfunction "6_6") (pintype "passive"))
      (node (ref "J5") (pin "6") (pinfunction "6_6") (pintype "passive"))
      (node (ref "J6") (pin "6") (pinfunction "6_6") (pintype "passive"))
      (node (ref "J7") (pin "6") (pinfunction "6_6") (pintype "passive"))
      (node (ref "J8") (pin "6") (pinfunction "6_6") (pintype "passive"))
      (node (ref "JP1") (pin "1") (pinfunction "1_1") (pintype "passive"))
      (node (ref "Q1") (pin "3") (pinfunction "D_3") (pintype "bidirectional"))
      (node (ref "U3") (pin "3") (pinfunction "~{CE}_3") (pintype "input"))
    )
    (net (code "45") (name "VIN") (class "Default")
      (node (ref "C12") (pin "2") (pinfunction "2_2") (pintype "passive"))
      (node (ref "JP1") (pin "2") (pinfunction "2_2") (pintype "passive"))
      (node (ref "Q1") (pin "2") (pinfunction "S_2") (pintype "bidirectional"))
      (node (ref "SJ1") (pin "2") (pinfunction "2_2") (pintype "passive"))
      (node (ref "U1") (pin "1") (pinfunction "VIN_1") (pintype "power_in"))
      (node (ref "U3") (pin "6") (pinfunction "VOUT_6") (pintype "output"))
    )
    (net (code "46") (name "VINUSB") (class "Default")
      (node (ref "D2") (pin "4") (pinfunction "P$4_4") (pintype "passive"))
      (node (ref "F2") (pin "1") (pinfunction "1_1") (pintype "bidirectional"))
      (node (ref "USB1") (pin "1") (pinfunction "VCC_1") (pintype "bidirectional"))
    )
    (net (code "47") (name "VUSB") (class "Default")
      (node (ref "C1") (pin "2") (pinfunction "2_2") (pintype "passive"))
      (node (ref "F2") (pin "2") (pinfunction "2_2") (pintype "bidirectional"))
      (node (ref "JP1") (pin "3") (pinfunction "3_3") (pintype "passive"))
      (node (ref "R9") (pin "1") (pinfunction "1_1") (pintype "passive"))
      (node (ref "U3") (pin "1") (pinfunction "VIN_1") (pintype "input"))
    )
    (net (code "48") (name "unconnected-(U3-NC-Pad4)") (class "Default")
      (node (ref "U3") (pin "4") (pinfunction "NC_4") (pintype "no_connect"))
    )
    (net (code "49") (name "unconnected-(U4-PA02(AIN0{slash}DAC)-Pad3)") (class "Default")
      (node (ref "U4") (pin "3") (pinfunction "PA02(AIN0/DAC)_3") (pintype "bidirectional"))
    )
    (net (code "50") (name "unconnected-(U4-PA03(AIN1{slash}REFA)-Pad4)") (class "Default")
      (node (ref "U4") (pin "4") (pinfunction "PA03(AIN1/REFA)_4") (pintype "bidirectional"))
    )
    (net (code "51") (name "unconnected-(U4-PA12(I2C{slash}SER2:0+)-Pad21)") (class "Default")
      (node (ref "U4") (pin "21") (pinfunction "PA12(I2C/SER2:0+)_21") (pintype "bidirectional"))
    )
    (net (code "52") (name "unconnected-(U4-PA14(XIN{slash}SER2:2+)-Pad23)") (class "Default")
      (node (ref "U4") (pin "23") (pinfunction "PA14(XIN/SER2:2+)_23") (pintype "bidirectional"))
    )
    (net (code "53") (name "unconnected-(U4-PA17(I2C{slash}SER1:1+)-Pad26)") (class "Default")
      (node (ref "U4") (pin "26") (pinfunction "PA17(I2C/SER1:1+)_26") (pintype "bidirectional"))
    )
    (net (code "54") (name "unconnected-(U4-PA18(SER1:2+)-Pad27)") (class "Default")
      (node (ref "U4") (pin "27") (pinfunction "PA18(SER1:2+)_27") (pintype "bidirectional"))
    )
    (net (code "55") (name "unconnected-(U4-PA19(SER1:3+)-Pad28)") (class "Default")
      (node (ref "U4") (pin "28") (pinfunction "PA19(SER1:3+)_28") (pintype "bidirectional"))
    )
    (net (code "56") (name "unconnected-(U4-PA20(SER5:2+)-Pad29)") (class "Default")
      (node (ref "U4") (pin "29") (pinfunction "PA20(SER5:2+)_29") (pintype "bidirectional"))
    )
    (net (code "57") (name "unconnected-(U4-PA21(SER5:3+)-Pad30)") (class "Default")
      (node (ref "U4") (pin "30") (pinfunction "PA21(SER5:3+)_30") (pintype "bidirectional"))
    )
    (net (code "58") (name "unconnected-(U4-PB02(AIN10{slash}SER5:0)-Pad47)") (class "Default")
      (node (ref "U4") (pin "47") (pinfunction "PB02(AIN10/SER5:0)_47") (pintype "bidirectional"))
    )
    (net (code "59") (name "unconnected-(USB1-ID-Pad4)") (class "Default")
      (node (ref "USB1") (pin "4") (pinfunction "ID_4") (pintype "bidirectional"))
    )
  )
)
